# 4_P2_LCD_SD.net
KiCad netlist of a schematic drawn in Altium Designer
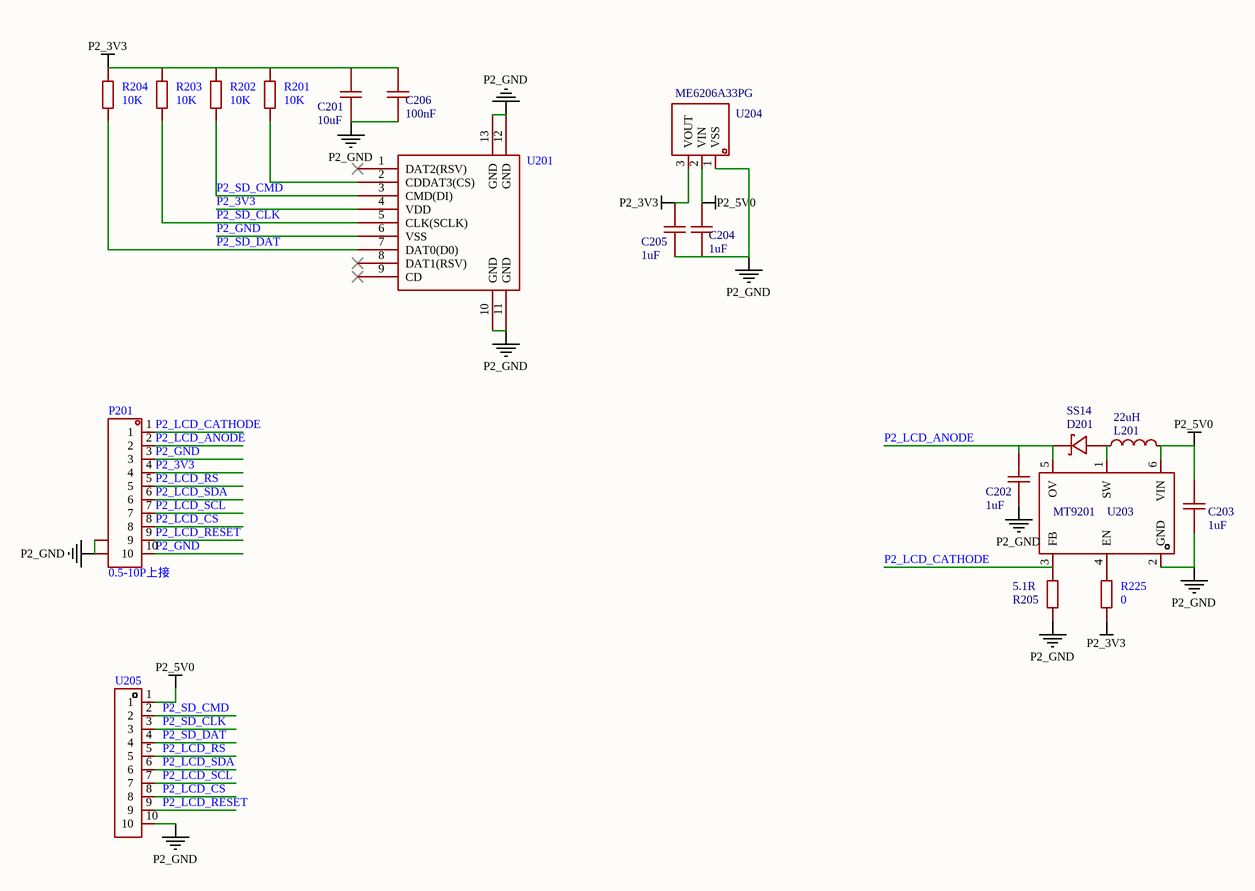
[diagram p0: 4_P2_LCD_SD.schdoc]

(export (version "E")
  (design (tool "Eeschema 10.0.6"))
  (components
    (comp (ref "C201")
      (value "10uF")
      (footprint "C0603")
      (libsource (lib "altium-import") (part "root_1_mirrored_CAP_0603_"))
    )
    (comp (ref "C202")
      (value "1uF")
      (footprint "C0805")
      (libsource (lib "altium-import") (part "root_1_mirrored_CAP_0603_"))
    )
    (comp (ref "C203")
      (value "1uF")
      (footprint "C0805")
      (libsource (lib "altium-import") (part "root_1_mirrored_CAP_0603_"))
    )
    (comp (ref "C204")
      (value "1uF")
      (footprint "C0603")
      (libsource (lib "altium-import") (part "root_1_mirrored_CAP_0603_"))
    )
    (comp (ref "C205")
      (value "1uF")
      (footprint "C0603")
      (libsource (lib "altium-import") (part "root_1_mirrored_CAP_0603_"))
    )
    (comp (ref "C206")
      (value "100nF")
      (footprint "C0603")
      (libsource (lib "altium-import") (part "root_1_mirrored_CAP_0603_"))
    )
    (comp (ref "D201")
      (value "SS14")
      (footprint "SMA_L4.3-W2.6-LS5.2-RD")
      (fields (field (name "MANUFACTURER") "星海"))
      (libsource (lib "altium-import") (part "root_2_mirrored_SS14_C84343_"))
    )
    (comp (ref "L201")
      (value "22uH")
      (footprint "IND-SMD_L4.0-W4.0")
      (fields
        (field (name "MANUFACTURER") "YJYCOIN(益嘉源)")
        (field (name "MANUFACTURER PART") "YNR4030-220M")
        (field (name "TOLERANCE") "±20%")
      )
      (libsource (lib "altium-import") (part "root_0_mirrored_YNR4030-220M_"))
    )
    (comp (ref "P201")
      (value "0.5-10P上接")
      (footprint "FPC_0.5_10P_mirror")
      (fields (field (name "MANUFACTURER") "BOOMELE(博穆精密)"))
      (libsource (lib "altium-import") (part "root_0_mirrored_0.5-10P上接_"))
    )
    (comp (ref "R201")
      (value "10K")
      (footprint "R0603")
      (libsource (lib "altium-import") (part "root_3_Res_0603_"))
    )
    (comp (ref "R202")
      (value "10K")
      (footprint "R0603")
      (libsource (lib "altium-import") (part "root_1_Res_0603_"))
    )
    (comp (ref "R203")
      (value "10K")
      (footprint "R0603")
      (libsource (lib "altium-import") (part "root_1_Res_0603_"))
    )
    (comp (ref "R204")
      (value "10K")
      (footprint "R0603")
      (libsource (lib "altium-import") (part "root_1_Res_0603_"))
    )
    (comp (ref "R205")
      (value "5.1R")
      (footprint "R0603")
      (libsource (lib "altium-import") (part "root_1_mirrored_Res_0603_"))
    )
    (comp (ref "R225")
      (value "0")
      (footprint "R0603")
      (libsource (lib "altium-import") (part "root_1_Res_0603_"))
    )
    (comp (ref "U201")
      (value "~")
      (footprint "TF-01A")
      (libsource (lib "altium-import") (part "root_0_TF-01A_"))
    )
    (comp (ref "U203")
      (value "~")
      (footprint "SOT-23-6_L2.9-W1.6-P0.95-LS2.8-BR")
      (fields (field (name "DEVICE") "MT9201"))
      (libsource (lib "altium-import") (part "root_0_mirrored_MT9201_"))
    )
    (comp (ref "U204")
      (value "ME6206A33PG")
      (footprint "SOT-89-3_L4.5-W2.5-P1.50-LS4.2-BR")
      (fields (field (name "MANUFACTURER") "MICRONE(南京微盟)") (field (name "MANUFACTURER PART") "ME6209A33PG"))
      (libsource (lib "altium-import") (part "root_0_mirrored_ME6209A33PG_"))
    )
    (comp (ref "U205")
      (value "~")
      (footprint "connector_p10_1.5mm")
      (libsource (lib "altium-import") (part "root_0_mirrored_connector_p10_1.5mm_"))
    )
  )
  (nets
    (net (code "1") (name "/P2_LCD_ANODE") (class "Default")
      (node (ref "C202") (pin "2") (pinfunction "2_2") (pintype "passive"))
      (node (ref "D201") (pin "1") (pinfunction "K_1") (pintype "passive"))
      (node (ref "P201") (pin "2") (pinfunction "2_2") (pintype "passive"))
      (node (ref "U203") (pin "5") (pinfunction "OV_5") (pintype "passive"))
    )
    (net (code "2") (name "/P2_LCD_CATHODE") (class "Default")
      (node (ref "P201") (pin "1") (pinfunction "1_1") (pintype "passive"))
      (node (ref "R205") (pin "2") (pinfunction "2_2") (pintype "passive"))
      (node (ref "U203") (pin "3") (pinfunction "FB_3") (pintype "passive"))
    )
    (net (code "3") (name "/P2_LCD_CS") (class "Default")
      (node (ref "P201") (pin "8") (pinfunction "8_8") (pintype "passive"))
      (node (ref "U205") (pin "8") (pinfunction "8_8") (pintype "passive"))
    )
    (net (code "4") (name "/P2_LCD_RESET") (class "Default")
      (node (ref "P201") (pin "9") (pinfunction "9_9") (pintype "passive"))
      (node (ref "U205") (pin "9") (pinfunction "9_9") (pintype "passive"))
    )
    (net (code "5") (name "/P2_LCD_RS") (class "Default")
      (node (ref "P201") (pin "5") (pinfunction "5_5") (pintype "passive"))
      (node (ref "U205") (pin "5") (pinfunction "5_5") (pintype "passive"))
    )
    (net (code "6") (name "/P2_LCD_SCL") (class "Default")
      (node (ref "P201") (pin "7") (pinfunction "7_7") (pintype "passive"))
      (node (ref "U205") (pin "7") (pinfunction "7_7") (pintype "passive"))
    )
    (net (code "7") (name "/P2_LCD_SDA") (class "Default")
      (node (ref "P201") (pin "6") (pinfunction "6_6") (pintype "passive"))
      (node (ref "U205") (pin "6") (pinfunction "6_6") (pintype "passive"))
    )
    (net (code "8") (name "/P2_SD_CLK") (class "Default")
      (node (ref "R203") (pin "1") (pinfunction "1_1") (pintype "passive"))
      (node (ref "U201") (pin "5") (pinfunction "CLK(SCLK)_5") (pintype "passive"))
      (node (ref "U205") (pin "3") (pinfunction "3_3") (pintype "passive"))
    )
    (net (code "9") (name "/P2_SD_CMD") (class "Default")
      (node (ref "R202") (pin "1") (pinfunction "1_1") (pintype "passive"))
      (node (ref "U201") (pin "3") (pinfunction "CMD(DI)_3") (pintype "passive"))
      (node (ref "U205") (pin "2") (pinfunction "2_2") (pintype "passive"))
    )
    (net (code "10") (name "/P2_SD_DAT") (class "Default")
      (node (ref "R204") (pin "1") (pinfunction "1_1") (pintype "passive"))
      (node (ref "U201") (pin "7") (pinfunction "DAT0(D0)_7") (pintype "passive"))
      (node (ref "U205") (pin "4") (pinfunction "4_4") (pintype "passive"))
    )
    (net (code "11") (name "Net-(D201-A)") (class "Default")
      (node (ref "D201") (pin "2") (pinfunction "A_2") (pintype "passive"))
      (node (ref "L201") (pin "2") (pinfunction "2_2") (pintype "passive"))
      (node (ref "U203") (pin "1") (pinfunction "SW_1") (pintype "passive"))
    )
    (net (code "12") (name "Net-(U201-CDDAT3(CS))") (class "Default")
      (node (ref "R201") (pin "2") (pinfunction "2_2") (pintype "passive"))
      (node (ref "U201") (pin "2") (pinfunction "CDDAT3(CS)_2") (pintype "passive"))
    )
    (net (code "13") (name "Net-(U203-EN)") (class "Default")
      (node (ref "R225") (pin "2") (pinfunction "2_2") (pintype "passive"))
      (node (ref "U203") (pin "4") (pinfunction "EN_4") (pintype "passive"))
    )
    (net (code "14") (name "P2_3V3") (class "Default")
      (node (ref "C201") (pin "2") (pinfunction "2_2") (pintype "passive"))
      (node (ref "C205") (pin "2") (pinfunction "2_2") (pintype "passive"))
      (node (ref "C206") (pin "2") (pinfunction "2_2") (pintype "passive"))
      (node (ref "P201") (pin "4") (pinfunction "4_4") (pintype "passive"))
      (node (ref "R201") (pin "1") (pinfunction "1_1") (pintype "passive"))
      (node (ref "R202") (pin "2") (pinfunction "2_2") (pintype "passive"))
      (node (ref "R203") (pin "2") (pinfunction "2_2") (pintype "passive"))
      (node (ref "R204") (pin "2") (pinfunction "2_2") (pintype "passive"))
      (node (ref "R225") (pin "1") (pinfunction "1_1") (pintype "passive"))
      (node (ref "U201") (pin "4") (pinfunction "VDD_4") (pintype "passive"))
      (node (ref "U204") (pin "3") (pinfunction "VOUT_3") (pintype "passive"))
    )
    (net (code "15") (name "P2_5V0") (class "Default")
      (node (ref "C203") (pin "2") (pinfunction "2_2") (pintype "passive"))
      (node (ref "C204") (pin "2") (pinfunction "2_2") (pintype "passive"))
      (node (ref "L201") (pin "1") (pinfunction "1_1") (pintype "passive"))
      (node (ref "U203") (pin "6") (pinfunction "VIN_6") (pintype "passive"))
      (node (ref "U204") (pin "2") (pinfunction "VIN_2") (pintype "passive"))
      (node (ref "U205") (pin "1") (pinfunction "1_1") (pintype "passive"))
    )
    (net (code "16") (name "P2_GND") (class "Default")
      (node (ref "C201") (pin "1") (pinfunction "1_1") (pintype "passive"))
      (node (ref "C202") (pin "1") (pinfunction "1_1") (pintype "passive"))
      (node (ref "C203") (pin "1") (pinfunction "1_1") (pintype "passive"))
      (node (ref "C204") (pin "1") (pinfunction "1_1") (pintype "passive"))
      (node (ref "C205") (pin "1") (pinfunction "1_1") (pintype "passive"))
      (node (ref "C206") (pin "1") (pinfunction "1_1") (pintype "passive"))
      (node (ref "P201") (pin "10") (pinfunction "10_10") (pintype "passive"))
      (node (ref "P201") (pin "11") (pinfunction "11_11") (pintype "passive"))
      (node (ref "P201") (pin "12") (pinfunction "12_12") (pintype "passive"))
      (node (ref "P201") (pin "3") (pinfunction "3_3") (pintype "passive"))
      (node (ref "R205") (pin "1") (pinfunction "1_1") (pintype "passive"))
      (node (ref "U201") (pin "10") (pinfunction "GND_10") (pintype "passive"))
      (node (ref "U201") (pin "11") (pinfunction "GND_11") (pintype "passive"))
      (node (ref "U201") (pin "12") (pinfunction "GND_12") (pintype "passive"))
      (node (ref "U201") (pin "13") (pinfunction "GND_13") (pintype "passive"))
      (node (ref "U201") (pin "6") (pinfunction "VSS_6") (pintype "passive"))
      (node (ref "U203") (pin "2") (pinfunction "GND_2") (pintype "passive"))
      (node (ref "U204") (pin "1") (pinfunction "VSS_1") (pintype "passive"))
      (node (ref "U205") (pin "10") (pinfunction "10_10") (pintype "passive"))
    )
    (net (code "17") (name "unconnected-(U201-CD-Pad9)") (class "Default")
      (node (ref "U201") (pin "9") (pinfunction "CD_9") (pintype "passive+no_connect"))
    )
    (net (code "18") (name "unconnected-(U201-DAT1(RSV)-Pad8)") (class "Default")
      (node (ref "U201") (pin "8") (pinfunction "DAT1(RSV)_8") (pintype "passive+no_connect"))
    )
    (net (code "19") (name "unconnected-(U201-DAT2(RSV)-Pad1)") (class "Default")
      (node (ref "U201") (pin "1") (pinfunction "DAT2(RSV)_1") (pintype "passive+no_connect"))
    )
  )
)
